# LoRa-E5-Click.net
KiCad netlist of a schematic drawn in EAGLE
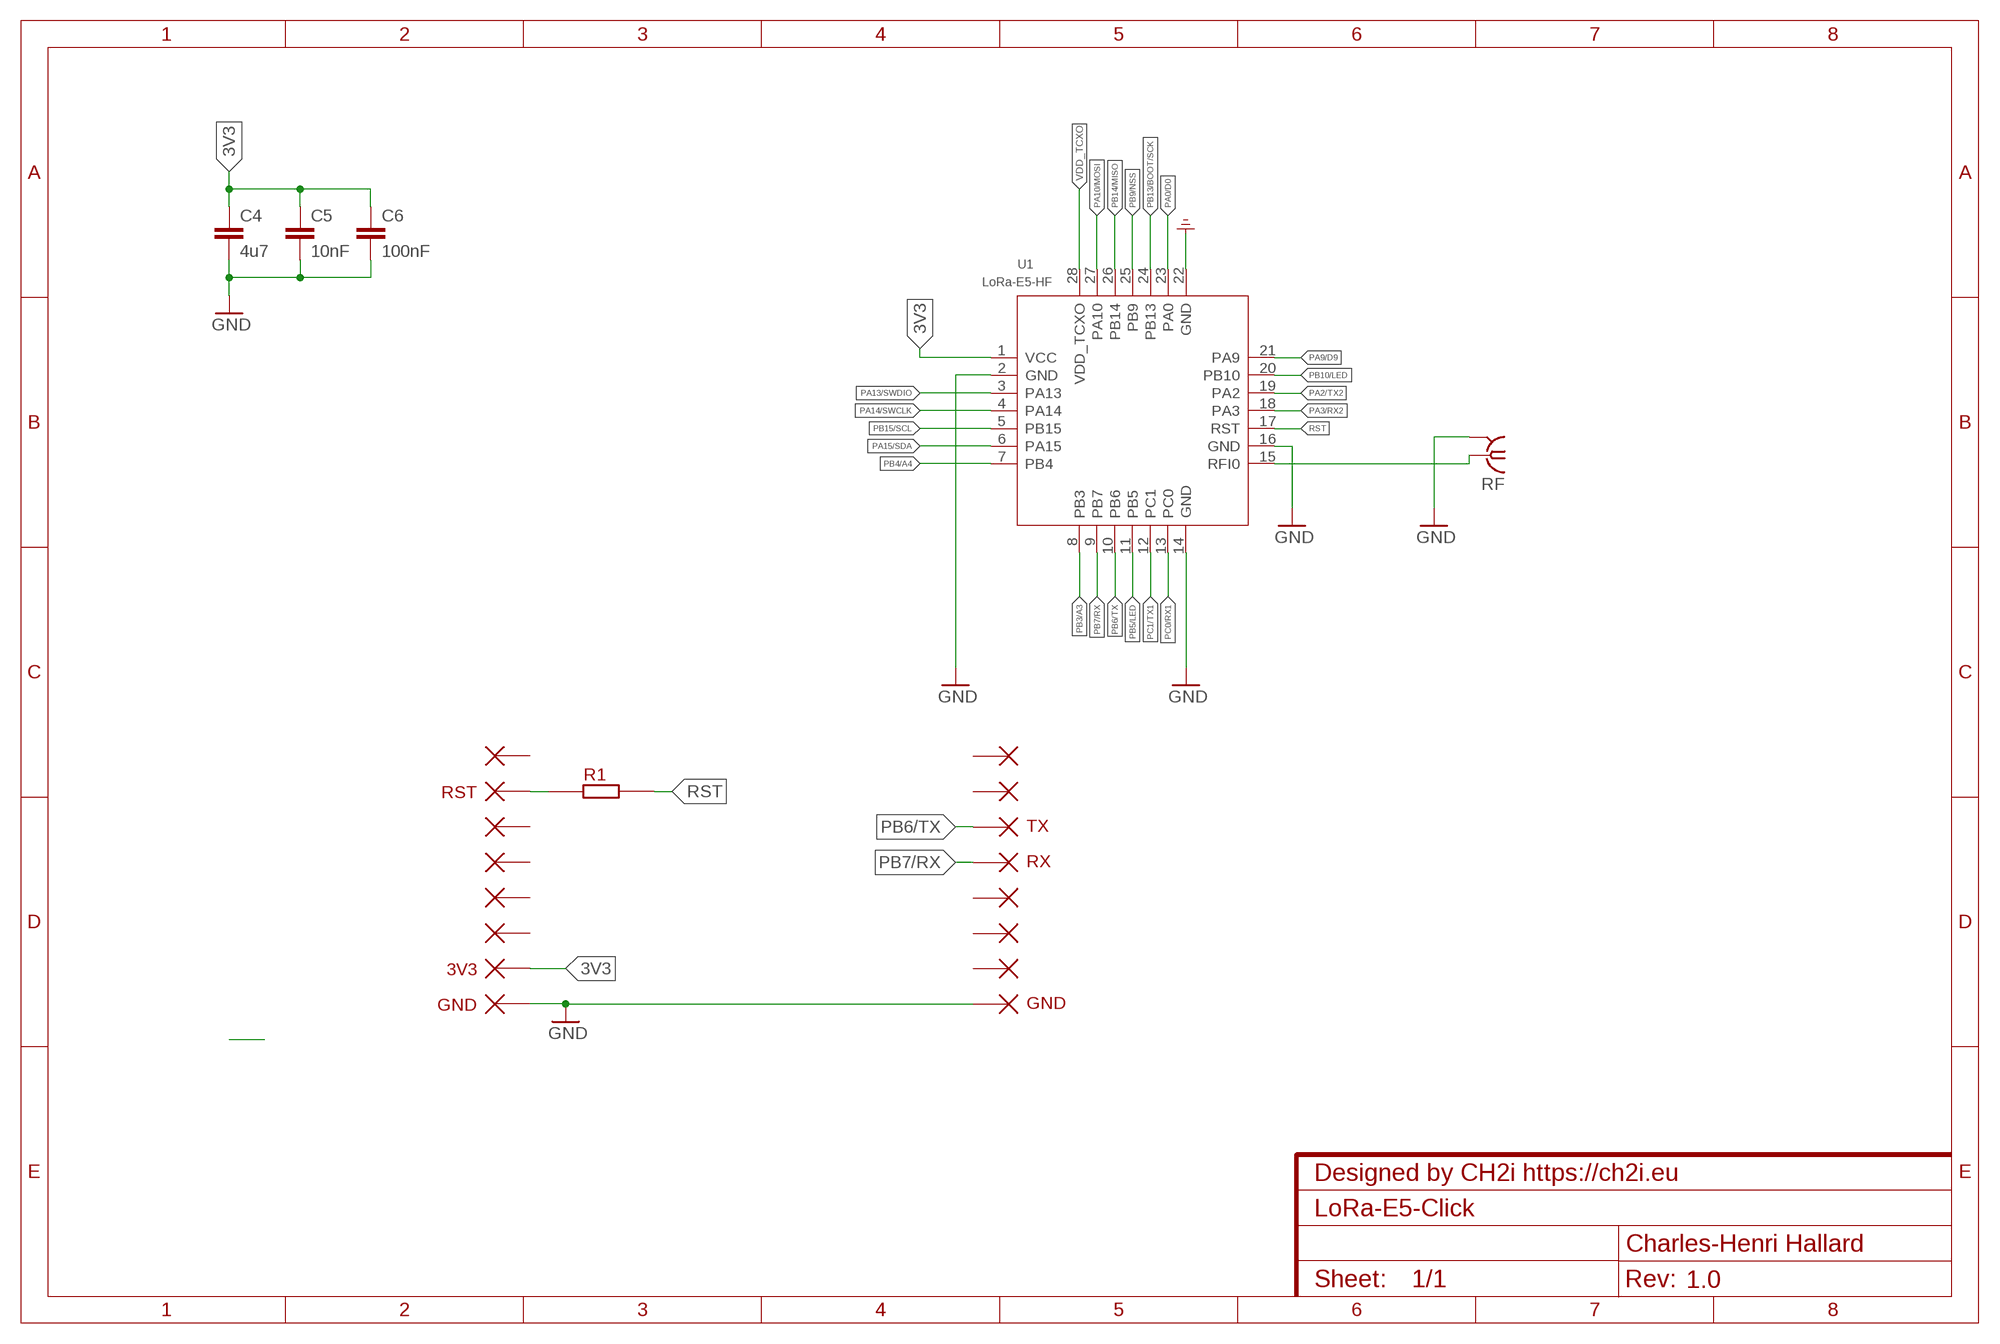
[diagram p0: schematic, sheet 1]

(export (version "E")
  (design (tool "Eeschema 10.0.6"))
  (components
    (comp (ref "C4")
      (value "4u7")
      (footprint "eagle-import:C1206")
      (libsource (lib "eagle-import") (part "SMD-C-1206"))
    )
    (comp (ref "C5")
      (value "10nF")
      (footprint "eagle-import:C1206")
      (libsource (lib "eagle-import") (part "SMD-C-1206"))
    )
    (comp (ref "C6")
      (value "100nF")
      (footprint "eagle-import:C1206")
      (libsource (lib "eagle-import") (part "SMD-C-1206"))
    )
    (comp (ref "P2")
      (value "PIN")
      (footprint "eagle-import:PIN")
      (libsource (lib "eagle-import") (part "PIN"))
    )
    (comp (ref "P3")
      (value "RST")
      (footprint "eagle-import:PIN")
      (libsource (lib "eagle-import") (part "PIN"))
    )
    (comp (ref "P7")
      (value "PIN")
      (footprint "eagle-import:PIN")
      (libsource (lib "eagle-import") (part "PIN"))
    )
    (comp (ref "P8")
      (value "PIN")
      (footprint "eagle-import:PIN")
      (libsource (lib "eagle-import") (part "PIN"))
    )
    (comp (ref "P9")
      (value "PIN")
      (footprint "eagle-import:PIN")
      (libsource (lib "eagle-import") (part "PIN"))
    )
    (comp (ref "P10")
      (value "PIN")
      (footprint "eagle-import:PIN")
      (libsource (lib "eagle-import") (part "PIN"))
    )
    (comp (ref "P11")
      (value "3V3")
      (footprint "eagle-import:PIN")
      (libsource (lib "eagle-import") (part "PIN"))
    )
    (comp (ref "P12")
      (value "GND")
      (footprint "eagle-import:PIN")
      (libsource (lib "eagle-import") (part "PIN"))
    )
    (comp (ref "P13")
      (value "PIN")
      (footprint "eagle-import:PIN")
      (libsource (lib "eagle-import") (part "PIN"))
    )
    (comp (ref "P14")
      (value "PIN")
      (footprint "eagle-import:PIN")
      (libsource (lib "eagle-import") (part "PIN"))
    )
    (comp (ref "P15")
      (value "TX")
      (footprint "eagle-import:PIN")
      (libsource (lib "eagle-import") (part "PIN"))
    )
    (comp (ref "P16")
      (value "RX")
      (footprint "eagle-import:PIN")
      (libsource (lib "eagle-import") (part "PIN"))
    )
    (comp (ref "P17")
      (value "PIN")
      (footprint "eagle-import:PIN")
      (libsource (lib "eagle-import") (part "PIN"))
    )
    (comp (ref "P18")
      (value "PIN")
      (footprint "eagle-import:PIN")
      (libsource (lib "eagle-import") (part "PIN"))
    )
    (comp (ref "P19")
      (value "PIN")
      (footprint "eagle-import:PIN")
      (libsource (lib "eagle-import") (part "PIN"))
    )
    (comp (ref "P20")
      (value "GND")
      (footprint "eagle-import:PIN")
      (libsource (lib "eagle-import") (part "PIN"))
    )
    (comp (ref "R1")
      (value "SMD-RR0603")
      (footprint "eagle-import:R0603")
      (libsource (lib "eagle-import") (part "SMD-RR0603"))
    )
    (comp (ref "RF")
      (value "SMAU.FL")
      (footprint "eagle-import:U.FL_SMT")
      (libsource (lib "eagle-import") (part "SMAU.FL"))
    )
    (comp (ref "U1")
      (value "LoRa-E5-HF")
      (footprint "eagle-import:MOUDLE28P-1.25-12X12X2.5MM")
      (libsource (lib "eagle-import") (part "MOUDLE_LORA_E5"))
    )
  )
  (nets
    (net (code "1") (name "3V3") (class "Default")
      (node (ref "C4") (pin "1") (pinfunction "1_1") (pintype "passive"))
      (node (ref "C5") (pin "1") (pinfunction "1_1") (pintype "passive"))
      (node (ref "C6") (pin "1") (pinfunction "1_1") (pintype "passive"))
      (node (ref "P11") (pin "P$1") (pinfunction "P$1_P$1") (pintype "bidirectional"))
      (node (ref "U1") (pin "1") (pinfunction "VCC_1") (pintype "bidirectional"))
    )
    (net (code "2") (name "GND") (class "Default")
      (node (ref "C4") (pin "2") (pinfunction "2_2") (pintype "passive"))
      (node (ref "C5") (pin "2") (pinfunction "2_2") (pintype "passive"))
      (node (ref "C6") (pin "2") (pinfunction "2_2") (pintype "passive"))
      (node (ref "P12") (pin "P$1") (pinfunction "P$1_P$1") (pintype "bidirectional"))
      (node (ref "P20") (pin "P$1") (pinfunction "P$1_P$1") (pintype "bidirectional"))
      (node (ref "RF") (pin "GND1") (pinfunction "SHIELD_GND1") (pintype "passive"))
      (node (ref "RF") (pin "GND2") (pinfunction "SHIELD_GND2") (pintype "passive"))
      (node (ref "U1") (pin "14") (pinfunction "GND_14") (pintype "bidirectional"))
      (node (ref "U1") (pin "16") (pinfunction "GND_16") (pintype "bidirectional"))
      (node (ref "U1") (pin "2") (pinfunction "GND_2") (pintype "bidirectional"))
      (node (ref "U1") (pin "22") (pinfunction "GND_22") (pintype "bidirectional"))
    )
    (net (code "3") (name "Net-(R1-P$1)") (class "Default")
      (node (ref "P3") (pin "P$1") (pinfunction "P$1_P$1") (pintype "bidirectional"))
      (node (ref "R1") (pin "1") (pinfunction "P$1_1") (pintype "passive"))
    )
    (net (code "4") (name "Net-(RF-ANT)") (class "Default")
      (node (ref "RF") (pin "SIG") (pinfunction "ANT_SIG") (pintype "passive"))
      (node (ref "U1") (pin "15") (pinfunction "RFI0_15") (pintype "bidirectional"))
    )
    (net (code "5") (name "PA0{slash}D0") (class "Default")
      (node (ref "U1") (pin "23") (pinfunction "PA0_23") (pintype "bidirectional"))
    )
    (net (code "6") (name "PA2{slash}TX2") (class "Default")
      (node (ref "U1") (pin "19") (pinfunction "PA2_19") (pintype "bidirectional"))
    )
    (net (code "7") (name "PA3{slash}RX2") (class "Default")
      (node (ref "U1") (pin "18") (pinfunction "PA3_18") (pintype "bidirectional"))
    )
    (net (code "8") (name "PA9{slash}D9") (class "Default")
      (node (ref "U1") (pin "21") (pinfunction "PA9_21") (pintype "bidirectional"))
    )
    (net (code "9") (name "PA10{slash}MOSI") (class "Default")
      (node (ref "U1") (pin "27") (pinfunction "PA10_27") (pintype "bidirectional"))
    )
    (net (code "10") (name "PA13{slash}SWDIO") (class "Default")
      (node (ref "U1") (pin "3") (pinfunction "PA13_3") (pintype "bidirectional"))
    )
    (net (code "11") (name "PA14{slash}SWCLK") (class "Default")
      (node (ref "U1") (pin "4") (pinfunction "PA14_4") (pintype "bidirectional"))
    )
    (net (code "12") (name "PA15{slash}SDA") (class "Default")
      (node (ref "U1") (pin "6") (pinfunction "PA15_6") (pintype "bidirectional"))
    )
    (net (code "13") (name "PB3{slash}A3") (class "Default")
      (node (ref "U1") (pin "8") (pinfunction "PB3_8") (pintype "bidirectional"))
    )
    (net (code "14") (name "PB4{slash}A4") (class "Default")
      (node (ref "U1") (pin "7") (pinfunction "PB4_7") (pintype "bidirectional"))
    )
    (net (code "15") (name "PB5{slash}LED") (class "Default")
      (node (ref "U1") (pin "11") (pinfunction "PB5_11") (pintype "bidirectional"))
    )
    (net (code "16") (name "PB6{slash}TX") (class "Default")
      (node (ref "P15") (pin "P$1") (pinfunction "P$1_P$1") (pintype "bidirectional"))
      (node (ref "U1") (pin "10") (pinfunction "PB6_10") (pintype "bidirectional"))
    )
    (net (code "17") (name "PB7{slash}RX") (class "Default")
      (node (ref "P16") (pin "P$1") (pinfunction "P$1_P$1") (pintype "bidirectional"))
      (node (ref "U1") (pin "9") (pinfunction "PB7_9") (pintype "bidirectional"))
    )
    (net (code "18") (name "PB9{slash}NSS") (class "Default")
      (node (ref "U1") (pin "25") (pinfunction "PB9_25") (pintype "bidirectional"))
    )
    (net (code "19") (name "PB10{slash}LED") (class "Default")
      (node (ref "U1") (pin "20") (pinfunction "PB10_20") (pintype "bidirectional"))
    )
    (net (code "20") (name "PB13{slash}BOOT{slash}SCK") (class "Default")
      (node (ref "U1") (pin "24") (pinfunction "PB13_24") (pintype "bidirectional"))
    )
    (net (code "21") (name "PB14{slash}MISO") (class "Default")
      (node (ref "U1") (pin "26") (pinfunction "PB14_26") (pintype "bidirectional"))
    )
    (net (code "22") (name "PB15{slash}SCL") (class "Default")
      (node (ref "U1") (pin "5") (pinfunction "PB15_5") (pintype "bidirectional"))
    )
    (net (code "23") (name "PC0{slash}RX1") (class "Default")
      (node (ref "U1") (pin "13") (pinfunction "PC0_13") (pintype "bidirectional"))
    )
    (net (code "24") (name "PC1{slash}TX1") (class "Default")
      (node (ref "U1") (pin "12") (pinfunction "PC1_12") (pintype "bidirectional"))
    )
    (net (code "25") (name "RST") (class "Default")
      (node (ref "R1") (pin "2") (pinfunction "P$3_2") (pintype "passive"))
      (node (ref "U1") (pin "17") (pinfunction "RST_17") (pintype "bidirectional"))
    )
    (net (code "26") (name "VDD_TCXO") (class "Default")
      (node (ref "U1") (pin "28") (pinfunction "VDD_TCXO_28") (pintype "bidirectional"))
    )
    (net (code "27") (name "unconnected-(P2-PadP$1)") (class "Default")
      (node (ref "P2") (pin "P$1") (pinfunction "P$1_P$1") (pintype "bidirectional"))
    )
    (net (code "28") (name "unconnected-(P7-PadP$1)") (class "Default")
      (node (ref "P7") (pin "P$1") (pinfunction "P$1_P$1") (pintype "bidirectional"))
    )
    (net (code "29") (name "unconnected-(P8-PadP$1)") (class "Default")
      (node (ref "P8") (pin "P$1") (pinfunction "P$1_P$1") (pintype "bidirectional"))
    )
    (net (code "30") (name "unconnected-(P9-PadP$1)") (class "Default")
      (node (ref "P9") (pin "P$1") (pinfunction "P$1_P$1") (pintype "bidirectional"))
    )
    (net (code "31") (name "unconnected-(P10-PadP$1)") (class "Default")
      (node (ref "P10") (pin "P$1") (pinfunction "P$1_P$1") (pintype "bidirectional"))
    )
    (net (code "32") (name "unconnected-(P13-PadP$1)") (class "Default")
      (node (ref "P13") (pin "P$1") (pinfunction "P$1_P$1") (pintype "bidirectional"))
    )
    (net (code "33") (name "unconnected-(P14-PadP$1)") (class "Default")
      (node (ref "P14") (pin "P$1") (pinfunction "P$1_P$1") (pintype "bidirectional"))
    )
    (net (code "34") (name "unconnected-(P17-PadP$1)") (class "Default")
      (node (ref "P17") (pin "P$1") (pinfunction "P$1_P$1") (pintype "bidirectional"))
    )
    (net (code "35") (name "unconnected-(P18-PadP$1)") (class "Default")
      (node (ref "P18") (pin "P$1") (pinfunction "P$1_P$1") (pintype "bidirectional"))
    )
    (net (code "36") (name "unconnected-(P19-PadP$1)") (class "Default")
      (node (ref "P19") (pin "P$1") (pinfunction "P$1_P$1") (pintype "bidirectional"))
    )
  )
)
